# Power.net
KiCad netlist of a schematic drawn in Altium Designer
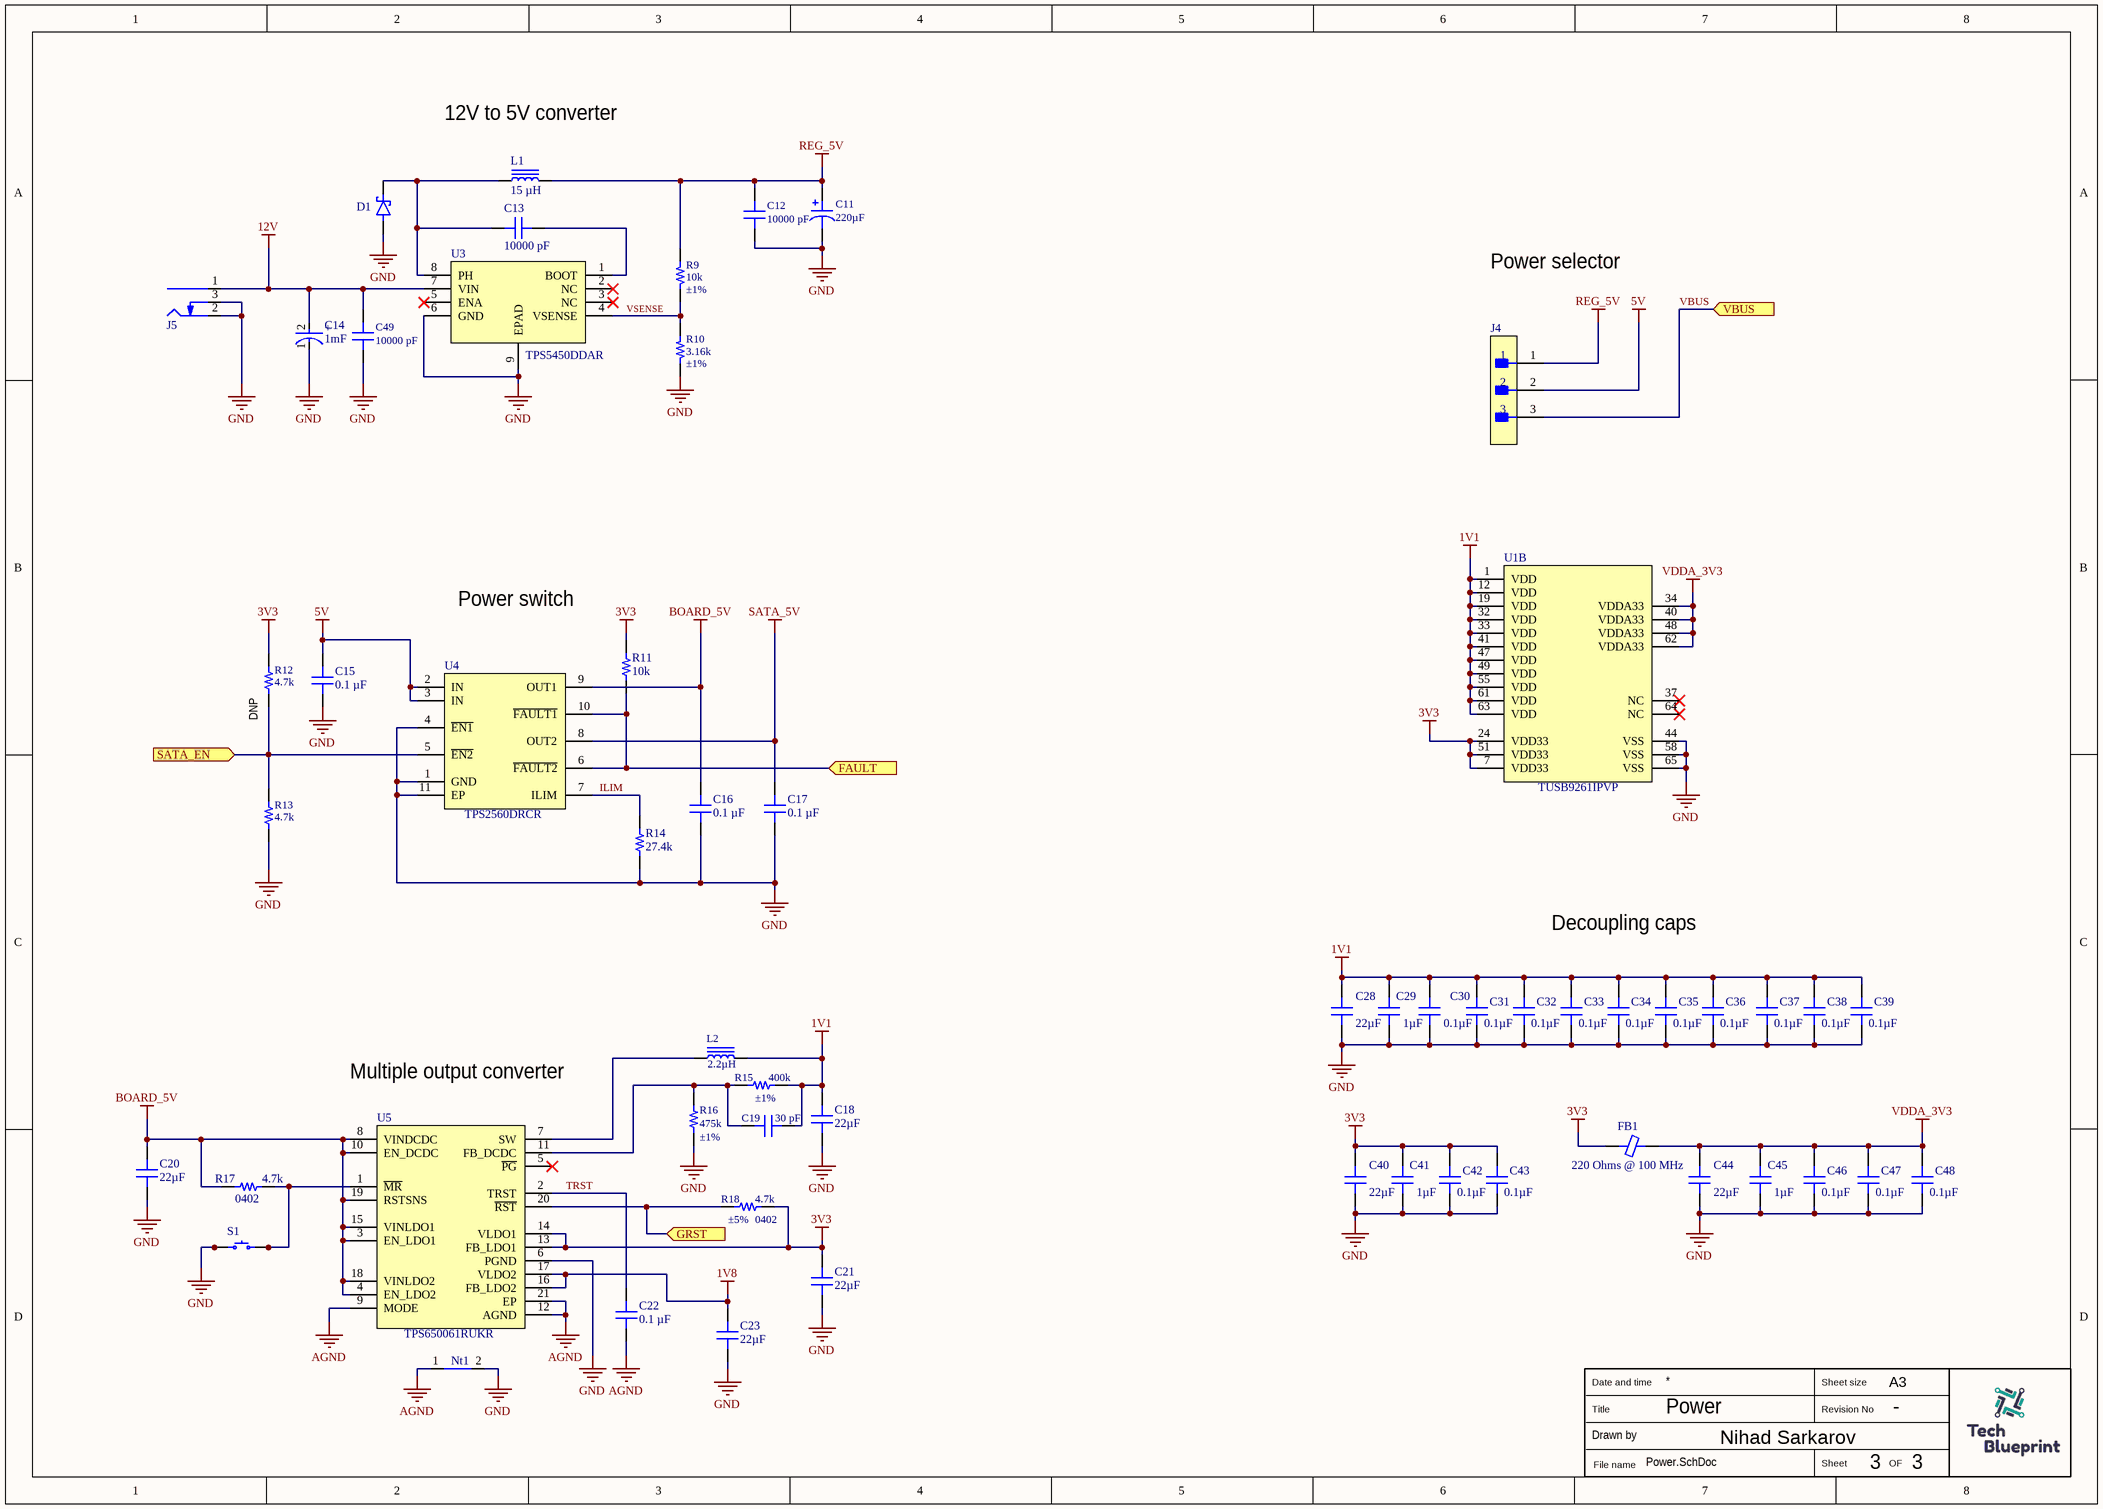
[diagram p0: Power.SchDoc]

(export (version "E")
  (design (tool "Eeschema 10.0.6"))
  (components
    (comp (ref "C11")
      (value "220µF")
      (footprint "CAP ALSMD 8.3MM H10.5MM")
      (description "CAP ALUM 220UF 20% 25V SMD")
      (fields (field (name "PART NUMBER") "UUR1E221MNL6GS") (field (name "MANUFACTURER") "Nichicon"))
      (libsource (lib "Celestial Altium Library - altium_library") (part "Polarised Capacitor"))
    )
    (comp (ref "C12")
      (value "10000 pF")
      (footprint "CAP 0805_2012")
      (description "CAP CER 0805 10NF 100V X7R")
      (fields
        (field (name "PART NUMBER") "C0805X103K1RAC3316")
        (field (name "CAPACITANCE") "10000 pF")
        (field (name "MANUFACTURER") "KEMET")
      )
      (libsource (lib "Celestial Altium Library - altium_library") (part "Capacitor"))
    )
    (comp (ref "C13")
      (value "10000 pF")
      (footprint "CAP 0805_2012")
      (description "CAP CER 0805 10NF 100V X7R")
      (fields
        (field (name "PART NUMBER") "C0805X103K1RAC3316")
        (field (name "CAPACITANCE") "10000 pF")
        (field (name "MANUFACTURER") "KEMET")
      )
      (libsource (lib "Celestial Altium Library - altium_library") (part "Capacitor"))
    )
    (comp (ref "C14")
      (value "EEEFT1C102AP")
      (footprint "FP-FTG-MFG")
      (description "CAP ALUM 1000UF 20% 16V SMD")
      (fields
        (field (name "TOLERANCE") "20%")
        (field (name "CAPACITANCE") "1mF")
        (field (name "VOLTAGE") "16V")
      )
      (libsource (lib "Altium Content Vault") (part "a00bbbee19879c290e62620ae7e47b1"))
    )
    (comp (ref "C15")
      (value "0.1 µF")
      (footprint "CAP 0603_1608")
      (description "CAP CER 0.1UF 50V X7R 0603")
      (fields
        (field (name "PART NUMBER") "CL10B104KB85PND")
        (field (name "CAPACITANCE") "0.1 µF")
        (field (name "MANUFACTURER") "Samsung Electro-Mechanics")
      )
      (libsource (lib "Celestial Altium Library - altium_library") (part "Capacitor"))
    )
    (comp (ref "C16")
      (value "0.1 µF")
      (footprint "CAP 0603_1608")
      (description "CAP CER 0.1UF 50V X7R 0603")
      (fields
        (field (name "PART NUMBER") "CL10B104KB85PND")
        (field (name "CAPACITANCE") "0.1 µF")
        (field (name "MANUFACTURER") "Samsung Electro-Mechanics")
      )
      (libsource (lib "Celestial Altium Library - altium_library") (part "Capacitor"))
    )
    (comp (ref "C17")
      (value "0.1 µF")
      (footprint "CAP 0603_1608")
      (description "CAP CER 0.1UF 50V X7R 0603")
      (fields
        (field (name "PART NUMBER") "CL10B104KB85PND")
        (field (name "CAPACITANCE") "0.1 µF")
        (field (name "MANUFACTURER") "Samsung Electro-Mechanics")
      )
      (libsource (lib "Celestial Altium Library - altium_library") (part "Capacitor"))
    )
    (comp (ref "C18")
      (value "22µF")
      (footprint "CAP 1206_3216 - 1.8MM")
      (description "CAP CER 22UF 16V X5R 1206")
      (fields
        (field (name "PART NUMBER") "1206YD226KAT2A")
        (field (name "CAPACITANCE") "22µF")
        (field (name "MANUFACTURER") "AVX Corporation")
      )
      (libsource (lib "Celestial Altium Library - altium_library") (part "Capacitor"))
    )
    (comp (ref "C19")
      (value "30 pF")
      (footprint "CAP 0402_1005")
      (description "CAP CER 30PF 50V NP0 0402")
      (fields
        (field (name "PART NUMBER") "C0402C300K5GAC7867")
        (field (name "CAPACITANCE") "30 pF")
        (field (name "MANUFACTURER") "KEMET")
      )
      (libsource (lib "Celestial Altium Library - altium_library") (part "Capacitor"))
    )
    (comp (ref "C20")
      (value "22µF")
      (footprint "CAP 1206_3216 - 1.8MM")
      (description "CAP CER 22UF 16V X5R 1206")
      (fields
        (field (name "PART NUMBER") "1206YD226KAT2A")
        (field (name "CAPACITANCE") "22µF")
        (field (name "MANUFACTURER") "AVX Corporation")
      )
      (libsource (lib "Celestial Altium Library - altium_library") (part "Capacitor"))
    )
    (comp (ref "C21")
      (value "22µF")
      (footprint "CAP 1206_3216 - 1.8MM")
      (description "CAP CER 22UF 16V X5R 1206")
      (fields
        (field (name "PART NUMBER") "1206YD226KAT2A")
        (field (name "CAPACITANCE") "22µF")
        (field (name "MANUFACTURER") "AVX Corporation")
      )
      (libsource (lib "Celestial Altium Library - altium_library") (part "Capacitor"))
    )
    (comp (ref "C22")
      (value "0.1 µF")
      (footprint "CAP 0603_1608")
      (description "CAP CER 0.1UF 50V X7R 0603")
      (fields
        (field (name "PART NUMBER") "CL10B104KB85PND")
        (field (name "CAPACITANCE") "0.1 µF")
        (field (name "MANUFACTURER") "Samsung Electro-Mechanics")
      )
      (libsource (lib "Celestial Altium Library - altium_library") (part "Capacitor"))
    )
    (comp (ref "C23")
      (value "22µF")
      (footprint "CAP 1206_3216 - 1.8MM")
      (description "CAP CER 22UF 16V X5R 1206")
      (fields
        (field (name "PART NUMBER") "1206YD226KAT2A")
        (field (name "CAPACITANCE") "22µF")
        (field (name "MANUFACTURER") "AVX Corporation")
      )
      (libsource (lib "Celestial Altium Library - altium_library") (part "Capacitor"))
    )
    (comp (ref "C28")
      (value "22µF")
      (footprint "CAP 1206_3216 - 1.8MM")
      (description "CAP CER 22UF 16V X5R 1206")
      (fields
        (field (name "PART NUMBER") "1206YD226KAT2A")
        (field (name "CAPACITANCE") "22µF")
        (field (name "MANUFACTURER") "AVX Corporation")
      )
      (libsource (lib "Celestial Altium Library - altium_library") (part "Capacitor"))
    )
    (comp (ref "C29")
      (value "1µF")
      (footprint "CAP 0805_2012")
      (description "CAP CER 1UF 10V X7R 0805")
      (fields
        (field (name "PART NUMBER") "MM05ZC105KCZ2A")
        (field (name "CAPACITANCE") "1µF")
        (field (name "MANUFACTURER") "AVX Corporation")
      )
      (libsource (lib "Celestial Altium Library - altium_library") (part "Capacitor"))
    )
    (comp (ref "C30")
      (value "0.1µF")
      (footprint "CAP 0805_2012")
      (description "CAP CER 0.1UF 25V X7R 0805")
      (fields
        (field (name "PART NUMBER") "08053C104KAT4A")
        (field (name "CAPACITANCE") "0.1µF")
        (field (name "MANUFACTURER") "AVX Corporation")
      )
      (libsource (lib "Celestial Altium Library - altium_library") (part "Capacitor"))
    )
    (comp (ref "C31")
      (value "0.1µF")
      (footprint "CAP 0603_1608")
      (description "CAP CER 0.1UF 25V X7R 0603")
      (fields
        (field (name "PART NUMBER") "06033C104K4T4A")
        (field (name "CAPACITANCE") "0.1µF")
        (field (name "MANUFACTURER") "AVX Corporation")
      )
      (libsource (lib "Celestial Altium Library - altium_library") (part "Capacitor"))
    )
    (comp (ref "C32")
      (value "0.1µF")
      (footprint "CAP 0603_1608")
      (description "CAP CER 0.1UF 25V X7R 0603")
      (fields
        (field (name "PART NUMBER") "06033C104K4T4A")
        (field (name "CAPACITANCE") "0.1µF")
        (field (name "MANUFACTURER") "AVX Corporation")
      )
      (libsource (lib "Celestial Altium Library - altium_library") (part "Capacitor"))
    )
    (comp (ref "C33")
      (value "0.1µF")
      (footprint "CAP 0603_1608")
      (description "CAP CER 0.1UF 25V X7R 0603")
      (fields
        (field (name "PART NUMBER") "06033C104K4T4A")
        (field (name "CAPACITANCE") "0.1µF")
        (field (name "MANUFACTURER") "AVX Corporation")
      )
      (libsource (lib "Celestial Altium Library - altium_library") (part "Capacitor"))
    )
    (comp (ref "C34")
      (value "0.1µF")
      (footprint "CAP 0603_1608")
      (description "CAP CER 0.1UF 25V X7R 0603")
      (fields
        (field (name "PART NUMBER") "06033C104K4T4A")
        (field (name "CAPACITANCE") "0.1µF")
        (field (name "MANUFACTURER") "AVX Corporation")
      )
      (libsource (lib "Celestial Altium Library - altium_library") (part "Capacitor"))
    )
    (comp (ref "C35")
      (value "0.1µF")
      (footprint "CAP 0603_1608")
      (description "CAP CER 0.1UF 25V X7R 0603")
      (fields
        (field (name "PART NUMBER") "06033C104K4T4A")
        (field (name "CAPACITANCE") "0.1µF")
        (field (name "MANUFACTURER") "AVX Corporation")
      )
      (libsource (lib "Celestial Altium Library - altium_library") (part "Capacitor"))
    )
    (comp (ref "C36")
      (value "0.1µF")
      (footprint "CAP 0603_1608")
      (description "CAP CER 0.1UF 25V X7R 0603")
      (fields
        (field (name "PART NUMBER") "06033C104K4T4A")
        (field (name "CAPACITANCE") "0.1µF")
        (field (name "MANUFACTURER") "AVX Corporation")
      )
      (libsource (lib "Celestial Altium Library - altium_library") (part "Capacitor"))
    )
    (comp (ref "C37")
      (value "0.1µF")
      (footprint "CAP 0603_1608")
      (description "CAP CER 0.1UF 25V X7R 0603")
      (fields
        (field (name "PART NUMBER") "06033C104K4T4A")
        (field (name "CAPACITANCE") "0.1µF")
        (field (name "MANUFACTURER") "AVX Corporation")
      )
      (libsource (lib "Celestial Altium Library - altium_library") (part "Capacitor"))
    )
    (comp (ref "C38")
      (value "0.1µF")
      (footprint "CAP 0603_1608")
      (description "CAP CER 0.1UF 25V X7R 0603")
      (fields
        (field (name "PART NUMBER") "06033C104K4T4A")
        (field (name "CAPACITANCE") "0.1µF")
        (field (name "MANUFACTURER") "AVX Corporation")
      )
      (libsource (lib "Celestial Altium Library - altium_library") (part "Capacitor"))
    )
    (comp (ref "C39")
      (value "0.1µF")
      (footprint "CAP 0603_1608")
      (description "CAP CER 0.1UF 25V X7R 0603")
      (fields
        (field (name "PART NUMBER") "06033C104K4T4A")
        (field (name "CAPACITANCE") "0.1µF")
        (field (name "MANUFACTURER") "AVX Corporation")
      )
      (libsource (lib "Celestial Altium Library - altium_library") (part "Capacitor"))
    )
    (comp (ref "C40")
      (value "22µF")
      (footprint "CAP 1206_3216 - 1.8MM")
      (description "CAP CER 22UF 16V X5R 1206")
      (fields
        (field (name "PART NUMBER") "1206YD226KAT2A")
        (field (name "CAPACITANCE") "22µF")
        (field (name "MANUFACTURER") "AVX Corporation")
      )
      (libsource (lib "Celestial Altium Library - altium_library") (part "Capacitor"))
    )
    (comp (ref "C41")
      (value "1µF")
      (footprint "CAP 0805_2012")
      (description "CAP CER 1UF 10V X7R 0805")
      (fields
        (field (name "PART NUMBER") "MM05ZC105KCZ2A")
        (field (name "CAPACITANCE") "1µF")
        (field (name "MANUFACTURER") "AVX Corporation")
      )
      (libsource (lib "Celestial Altium Library - altium_library") (part "Capacitor"))
    )
    (comp (ref "C42")
      (value "0.1µF")
      (footprint "CAP 0603_1608")
      (description "CAP CER 0.1UF 25V X7R 0603")
      (fields
        (field (name "PART NUMBER") "06033C104K4T4A")
        (field (name "CAPACITANCE") "0.1µF")
        (field (name "MANUFACTURER") "AVX Corporation")
      )
      (libsource (lib "Celestial Altium Library - altium_library") (part "Capacitor"))
    )
    (comp (ref "C43")
      (value "0.1µF")
      (footprint "CAP 0603_1608")
      (description "CAP CER 0.1UF 25V X7R 0603")
      (fields
        (field (name "PART NUMBER") "06033C104K4T4A")
        (field (name "CAPACITANCE") "0.1µF")
        (field (name "MANUFACTURER") "AVX Corporation")
      )
      (libsource (lib "Celestial Altium Library - altium_library") (part "Capacitor"))
    )
    (comp (ref "C44")
      (value "22µF")
      (footprint "CAP 1206_3216 - 1.8MM")
      (description "CAP CER 22UF 16V X5R 1206")
      (fields
        (field (name "PART NUMBER") "1206YD226KAT2A")
        (field (name "CAPACITANCE") "22µF")
        (field (name "MANUFACTURER") "AVX Corporation")
      )
      (libsource (lib "Celestial Altium Library - altium_library") (part "Capacitor"))
    )
    (comp (ref "C45")
      (value "1µF")
      (footprint "CAP 0805_2012")
      (description "CAP CER 1UF 10V X7R 0805")
      (fields
        (field (name "PART NUMBER") "MM05ZC105KCZ2A")
        (field (name "CAPACITANCE") "1µF")
        (field (name "MANUFACTURER") "AVX Corporation")
      )
      (libsource (lib "Celestial Altium Library - altium_library") (part "Capacitor"))
    )
    (comp (ref "C46")
      (value "0.1µF")
      (footprint "CAP 0603_1608")
      (description "CAP CER 0.1UF 25V X7R 0603")
      (fields
        (field (name "PART NUMBER") "06033C104K4T4A")
        (field (name "CAPACITANCE") "0.1µF")
        (field (name "MANUFACTURER") "AVX Corporation")
      )
      (libsource (lib "Celestial Altium Library - altium_library") (part "Capacitor"))
    )
    (comp (ref "C47")
      (value "0.1µF")
      (footprint "CAP 0603_1608")
      (description "CAP CER 0.1UF 25V X7R 0603")
      (fields
        (field (name "PART NUMBER") "06033C104K4T4A")
        (field (name "CAPACITANCE") "0.1µF")
        (field (name "MANUFACTURER") "AVX Corporation")
      )
      (libsource (lib "Celestial Altium Library - altium_library") (part "Capacitor"))
    )
    (comp (ref "C48")
      (value "0.1µF")
      (footprint "CAP 0603_1608")
      (description "CAP CER 0.1UF 25V X7R 0603")
      (fields
        (field (name "PART NUMBER") "06033C104K4T4A")
        (field (name "CAPACITANCE") "0.1µF")
        (field (name "MANUFACTURER") "AVX Corporation")
      )
      (libsource (lib "Celestial Altium Library - altium_library") (part "Capacitor"))
    )
    (comp (ref "C49")
      (value "10000 pF")
      (footprint "CAP 0805_2012")
      (description "CAP CER 0805 10NF 100V X7R")
      (fields
        (field (name "PART NUMBER") "C0805X103K1RAC3316")
        (field (name "CAPACITANCE") "10000 pF")
        (field (name "MANUFACTURER") "KEMET")
      )
      (libsource (lib "Celestial Altium Library - altium_library") (part "Capacitor"))
    )
    (comp (ref "D1")
      (value "MBRS540T3G")
      (footprint "MBRS540T3G:DIOM7959X261N")
      (fields (field (name "MF") "{'manufacturer': u'ON Semiconductor'}"))
      (libsource (lib "USB to SATA") (part "MBRS540T3G"))
    )
    (comp (ref "FB1")
      (value "220 Ohms @ 100 MHz")
      (footprint "FER 0603_1608")
      (description "POWER LINE HIGH IMPEDANCE FERRIT")
      (fields (field (name "PART NUMBER") "Z0603C221BPWZT") (field (name "MANUFACTURER") "KEMET"))
      (libsource (lib "Celestial Altium Library - altium_library") (part "Ferrite Chip"))
    )
    (comp (ref "J4")
      (value "87224-3")
      (footprint "FP-87224-3-MFG")
      (description "CONN HEADER VERT 3POS 2.54MM")
      (libsource (lib "USB to SATA") (part "CMP-2000-05697-2"))
    )
    (comp (ref "J5")
      (value "PJ-002AH-SMT-TR")
      (footprint "CUI PJ-002AH-SMT-TR")
      (description "CONN PWR JACK 2X5.5MM SOLDER")
      (fields (field (name "MANUFACTURER") "CUI Devices"))
      (libsource (lib "Celestial Altium Library - altium_library") (part "Barrel Connector"))
    )
    (comp (ref "L1")
      (value "15 µH")
      (footprint "BOURNS SRR1280")
      (description "FIXED IND 15UH 5.2A 28.5MOHM SMD")
      (fields (field (name "PART NUMBER") "SRR1280-150M") (field (name "MANUFACTURER") "Bourns Inc."))
      (libsource (lib "") (part "Inductor_1"))
    )
    (comp (ref "L2")
      (value "2.2µH")
      (footprint "IND 1008_2520")
      (description "FIXED IND 2.2UH 700MA 150 MOHM")
      (fields (field (name "PART NUMBER") "CKP2520V2R2M-T") (field (name "MANUFACTURER") "Taiyo Yuden"))
      (libsource (lib "Celestial Altium Library - altium_library") (part "Inductor"))
    )
    (comp (ref "Nt1")
      (value "Net tie")
      (footprint "Net tie")
      (description "Net tie SMD")
      (libsource (lib "USB to SATA") (part "Net tie"))
    )
    (comp (ref "R9")
      (value "10k")
      (footprint "YAGEO RES 0603_1608")
      (description "RES SMD 10K OHM 1% 1/10W 0603")
      (fields
        (field (name "PART NUMBER") "RT0603FRE0710KL")
        (field (name "MANUFACTURER") "Yageo")
        (field (name "TOLERANCE") "±1%")
      )
      (libsource (lib "Celestial Altium Library - altium_library") (part "Resistor"))
    )
    (comp (ref "R10")
      (value "3.16k")
      (footprint "RES 0603_1608")
      (description "RES SMD 3.16K OHM 1% 1/10W 0603")
      (fields
        (field (name "PART NUMBER") "CR0603-FX-3161ELF")
        (field (name "MANUFACTURER") "Bourns Inc.")
        (field (name "TOLERANCE") "±1%")
      )
      (libsource (lib "Celestial Altium Library - altium_library") (part "Resistor"))
    )
    (comp (ref "R11")
      (value "10k")
      (footprint "YAGEO RES 0402_1005")
      (description "RES SMD 10K OHM 5% 1/16W 0402")
      (fields (field (name "PART NUMBER") "AC0402JR-0710KL") (field (name "MANUFACTURER") "Yageo"))
      (libsource (lib "Celestial Altium Library - altium_library") (part "Resistor"))
    )
    (comp (ref "R12")
      (value "4.7k")
      (footprint "RES 0603_1608")
      (description "RES 4.7K OHM 5% 1/10W 0603")
      (fields
        (field (name "PART NUMBER") "RMCF0603JT4K70")
        (field (name "MANUFACTURER") "Stackpole Electronics Inc")
      )
      (libsource (lib "Celestial Altium Library - altium_library") (part "Resistor"))
    )
    (comp (ref "R13")
      (value "4.7k")
      (footprint "RES 0603_1608")
      (description "RES 4.7K OHM 5% 1/10W 0603")
      (fields
        (field (name "PART NUMBER") "RMCF0603JT4K70")
        (field (name "MANUFACTURER") "Stackpole Electronics Inc")
      )
      (libsource (lib "Celestial Altium Library - altium_library") (part "Resistor"))
    )
    (comp (ref "R14")
      (value "27.4k")
      (footprint "RES 0402_1005")
      (description "RES SMD 27.4K OHM 1% 1/10W 0402")
      (fields
        (field (name "PART NUMBER") "ERJ-2RKF2742X")
        (field (name "MANUFACTURER") "Panasonic Electronic Components")
      )
      (libsource (lib "Celestial Altium Library - altium_library") (part "Resistor"))
    )
    (comp (ref "R15")
      (value "400k")
      (footprint "KOA RES RK73 RN73 0402_1005")
      (description "RES 400K OHM 1% 1/10W 0402")
      (fields
        (field (name "PART NUMBER") "RK73H1ETTP4123F")
        (field (name "MANUFACTURER") "KOA Speer Electronics, Inc.")
        (field (name "TOLERANCE") "±1%")
      )
      (libsource (lib "Celestial Altium Library - altium_library") (part "Resistor"))
    )
    (comp (ref "R16")
      (value "475k")
      (footprint "RES 0402_1005")
      (description "RES 475K OHM 1% 1/16W 0402")
      (fields
        (field (name "PART NUMBER") "RMCF0402FT475K")
        (field (name "MANUFACTURER") "Stackpole Electronics Inc")
        (field (name "TOLERANCE") "±1%")
      )
      (libsource (lib "Celestial Altium Library - altium_library") (part "Resistor"))
    )
    (comp (ref "R17")
      (value "4.7k")
      (footprint "YAGEO RES 0402_1005")
      (description "RES SMD 4.7K OHM 5% 1/16W 0402")
      (fields
        (field (name "PART NUMBER") "AC0402JR-074K7L")
        (field (name "MANUFACTURER") "Yageo")
        (field (name "SUPPLIER DEVICE PACKAGE") "0402")
      )
      (libsource (lib "Celestial Altium Library - altium_library") (part "Resistor"))
    )
    (comp (ref "R18")
      (value "4.7k")
      (footprint "YAGEO RES 0402_1005")
      (description "RES SMD 4.7K OHM 5% 1/16W 0402")
      (fields
        (field (name "PART NUMBER") "AC0402JR-074K7L")
        (field (name "MANUFACTURER") "Yageo")
        (field (name "SUPPLIER DEVICE PACKAGE") "0402")
        (field (name "TOLERANCE") "±5%")
      )
      (libsource (lib "Celestial Altium Library - altium_library") (part "Resistor"))
    )
    (comp (ref "S1")
      (value "PTS645SM43SMTR92 LFS")
      (footprint "C&K PTS645")
      (description "SWITCH TACTILE SPST-NO 0.05A 12V")
      (fields (field (name "MANUFACTURER") "C&K"))
      (libsource (lib "Celestial Altium Library - altium_library") (part "SPST-NO 4 PIN"))
    )
    (comp (ref "U1")
      (value "TUSB9261IPVP")
      (footprint "FP-PVP0064A-IPC_A")
      (description "HDD, CD, DVD Drive Interface 64-HTQFP (7x7)")
      (fields
        (field (name "MANUFACTURER") "Texas Instruments")
        (field (name "DIGIKEY PART NUMBER") "296-35545-ND")
      )
      (libsource (lib "USB to SATA") (part "TUSB9261IPVP"))
    )
    (comp (ref "U3")
      (value "TPS5450DDAR")
      (footprint "FP-DDA0008J-IPC_A")
      (description "IC REG BUCK ADJUSTABLE 5A 8SOPWR")
      (fields
        (field (name "MANUFACTURER") "Texas Instruments")
        (field (name "OCTOPART") "https://octopart.com/tps5450ddar-texas+instruments-7105511")
      )
      (libsource (lib "USB to SATA") (part "CMP-04918-000100-1"))
    )
    (comp (ref "U4")
      (value "TPS2560DRCR")
      (footprint "FP-DRC0010J-IPC_A")
      (description "IC PWR SWITCH N-CHAN 1:2 10VSON")
      (libsource (lib "USB to SATA") (part "CMP-0337-00200-3"))
    )
    (comp (ref "U5")
      (value "TPS650061RUKR")
      (footprint "RUK0020B")
      (fields (field (name "MANUFACTURER") "Texas Instruments"))
      (libsource (lib "USB to SATA") (part "CMP-1518-00013-2"))
    )
  )
  (nets
    (net (code "1") (name "/FAULT") (class "Default")
      (node (ref "R11") (pin "1") (pinfunction "1_1") (pintype "passive"))
      (node (ref "U4") (pin "10") (pinfunction "~{FAULT1}_10") (pintype "tri_state"))
      (node (ref "U4") (pin "6") (pinfunction "~{FAULT2}_6") (pintype "tri_state"))
    )
    (net (code "2") (name "/GRST") (class "Default")
      (node (ref "R18") (pin "1") (pinfunction "1_1") (pintype "passive"))
      (node (ref "U5") (pin "20") (pinfunction "~{RST}_20") (pintype "passive"))
    )
    (net (code "3") (name "/ILIM") (class "Default")
      (node (ref "R14") (pin "2") (pinfunction "2_2") (pintype "passive"))
      (node (ref "U4") (pin "7") (pinfunction "ILIM_7") (pintype "passive"))
    )
    (net (code "4") (name "/SATA_EN") (class "Default")
      (node (ref "R12") (pin "1") (pinfunction "1_1") (pintype "passive"))
      (node (ref "R13") (pin "2") (pinfunction "2_2") (pintype "passive"))
      (node (ref "U4") (pin "5") (pinfunction "~{EN2}_5") (pintype "passive"))
    )
    (net (code "5") (name "/TRST") (class "Default")
      (node (ref "C22") (pin "2") (pinfunction "2_2") (pintype "passive"))
      (node (ref "U5") (pin "2") (pinfunction "TRST_2") (pintype "passive"))
    )
    (net (code "6") (name "/VBUS") (class "Default")
      (node (ref "J4") (pin "3") (pinfunction "3_3") (pintype "passive"))
    )
    (net (code "7") (name "/VSENSE") (class "Default")
      (node (ref "R10") (pin "2") (pinfunction "2_2") (pintype "passive"))
      (node (ref "R9") (pin "1") (pinfunction "1_1") (pintype "passive"))
      (node (ref "U3") (pin "4") (pinfunction "VSENSE_4") (pintype "passive"))
    )
    (net (code "8") (name "1V1") (class "Default")
      (node (ref "C18") (pin "2") (pinfunction "2_2") (pintype "passive"))
      (node (ref "C19") (pin "2") (pinfunction "2_2") (pintype "passive"))
      (node (ref "C28") (pin "2") (pinfunction "2_2") (pintype "passive"))
      (node (ref "C29") (pin "2") (pinfunction "2_2") (pintype "passive"))
      (node (ref "C30") (pin "2") (pinfunction "2_2") (pintype "passive"))
      (node (ref "C31") (pin "2") (pinfunction "2_2") (pintype "passive"))
      (node (ref "C32") (pin "2") (pinfunction "2_2") (pintype "passive"))
      (node (ref "C33") (pin "2") (pinfunction "2_2") (pintype "passive"))
      (node (ref "C34") (pin "2") (pinfunction "2_2") (pintype "passive"))
      (node (ref "C35") (pin "2") (pinfunction "2_2") (pintype "passive"))
      (node (ref "C36") (pin "2") (pinfunction "2_2") (pintype "passive"))
      (node (ref "C37") (pin "2") (pinfunction "2_2") (pintype "passive"))
      (node (ref "C38") (pin "2") (pinfunction "2_2") (pintype "passive"))
      (node (ref "C39") (pin "2") (pinfunction "2_2") (pintype "passive"))
      (node (ref "L2") (pin "2") (pinfunction "2_2") (pintype "passive"))
      (node (ref "R15") (pin "2") (pinfunction "2_2") (pintype "passive"))
      (node (ref "U1") (pin "1") (pinfunction "VDD_1") (pintype "passive"))
      (node (ref "U1") (pin "12") (pinfunction "VDD_12") (pintype "passive"))
      (node (ref "U1") (pin "19") (pinfunction "VDD_19") (pintype "passive"))
      (node (ref "U1") (pin "32") (pinfunction "VDD_32") (pintype "passive"))
      (node (ref "U1") (pin "33") (pinfunction "VDD_33") (pintype "passive"))
      (node (ref "U1") (pin "41") (pinfunction "VDD_41") (pintype "passive"))
      (node (ref "U1") (pin "47") (pinfunction "VDD_47") (pintype "passive"))
      (node (ref "U1") (pin "49") (pinfunction "VDD_49") (pintype "passive"))
      (node (ref "U1") (pin "55") (pinfunction "VDD_55") (pintype "passive"))
      (node (ref "U1") (pin "61") (pinfunction "VDD_61") (pintype "passive"))
      (node (ref "U1") (pin "63") (pinfunction "VDD_63") (pintype "passive"))
    )
    (net (code "9") (name "1V8") (class "Default")
      (node (ref "C23") (pin "2") (pinfunction "2_2") (pintype "passive"))
      (node (ref "U5") (pin "16") (pinfunction "FB_LDO2_16") (pintype "passive"))
      (node (ref "U5") (pin "17") (pinfunction "VLDO2_17") (pintype "passive"))
    )
    (net (code "10") (name "3V3") (class "Default")
      (node (ref "C21") (pin "2") (pinfunction "2_2") (pintype "passive"))
      (node (ref "C40") (pin "2") (pinfunction "2_2") (pintype "passive"))
      (node (ref "C41") (pin "2") (pinfunction "2_2") (pintype "passive"))
      (node (ref "C42") (pin "2") (pinfunction "2_2") (pintype "passive"))
      (node (ref "C43") (pin "2") (pinfunction "2_2") (pintype "passive"))
      (node (ref "FB1") (pin "1") (pinfunction "1_1") (pintype "passive"))
      (node (ref "R11") (pin "2") (pinfunction "2_2") (pintype "passive"))
      (node (ref "R12") (pin "2") (pinfunction "2_2") (pintype "passive"))
      (node (ref "R18") (pin "2") (pinfunction "2_2") (pintype "passive"))
      (node (ref "U1") (pin "24") (pinfunction "VDD33_24") (pintype "passive"))
      (node (ref "U1") (pin "51") (pinfunction "VDD33_51") (pintype "passive"))
      (node (ref "U1") (pin "7") (pinfunction "VDD33_7") (pintype "passive"))
      (node (ref "U5") (pin "13") (pinfunction "FB_LDO1_13") (pintype "passive"))
      (node (ref "U5") (pin "14") (pinfunction "VLDO1_14") (pintype "passive"))
    )
    (net (code "11") (name "5V") (class "Default")
      (node (ref "C15") (pin "2") (pinfunction "2_2") (pintype "passive"))
      (node (ref "J4") (pin "2") (pinfunction "2_2") (pintype "passive"))
      (node (ref "U4") (pin "2") (pinfunction "IN_2") (pintype "power_in"))
      (node (ref "U4") (pin "3") (pinfunction "IN_3") (pintype "power_in"))
    )
    (net (code "12") (name "12V") (class "Default")
      (node (ref "C14") (pin "2") (pinfunction "A_2") (pintype "passive"))
      (node (ref "C49") (pin "2") (pinfunction "2_2") (pintype "passive"))
      (node (ref "J5") (pin "1") (pinfunction "Centre_1") (pintype "passive"))
      (node (ref "U3") (pin "7") (pinfunction "VIN_7") (pintype "passive"))
    )
    (net (code "13") (name "AGND") (class "Default")
      (node (ref "C22") (pin "1") (pinfunction "1_1") (pintype "passive"))
      (node (ref "Nt1") (pin "1") (pinfunction "1_1") (pintype "passive"))
      (node (ref "U5") (pin "12") (pinfunction "AGND_12") (pintype "passive"))
      (node (ref "U5") (pin "21") (pinfunction "EP_21") (pintype "passive"))
      (node (ref "U5") (pin "9") (pinfunction "MODE_9") (pintype "passive"))
    )
    (net (code "14") (name "BOARD_5V") (class "Default")
      (node (ref "C16") (pin "2") (pinfunction "2_2") (pintype "passive"))
      (node (ref "C20") (pin "2") (pinfunction "2_2") (pintype "passive"))
      (node (ref "R17") (pin "1") (pinfunction "1_1") (pintype "passive"))
      (node (ref "U4") (pin "9") (pinfunction "OUT1_9") (pintype "passive"))
      (node (ref "U5") (pin "10") (pinfunction "EN_DCDC_10") (pintype "passive"))
      (node (ref "U5") (pin "15") (pinfunction "VINLDO1_15") (pintype "passive"))
      (node (ref "U5") (pin "18") (pinfunction "VINLDO2_18") (pintype "passive"))
      (node (ref "U5") (pin "19") (pinfunction "RSTSNS_19") (pintype "passive"))
      (node (ref "U5") (pin "3") (pinfunction "EN_LDO1_3") (pintype "passive"))
      (node (ref "U5") (pin "4") (pinfunction "EN_LDO2_4") (pintype "passive"))
      (node (ref "U5") (pin "8") (pinfunction "VINDCDC_8") (pintype "passive"))
    )
    (net (code "15") (name "GND") (class "Default")
      (node (ref "C11") (pin "2") (pinfunction "2_2") (pintype "passive"))
      (node (ref "C12") (pin "1") (pinfunction "1_1") (pintype "passive"))
      (node (ref "C14") (pin "1") (pinfunction "C_1") (pintype "passive"))
      (node (ref "C15") (pin "1") (pinfunction "1_1") (pintype "passive"))
      (node (ref "C16") (pin "1") (pinfunction "1_1") (pintype "passive"))
      (node (ref "C17") (pin "1") (pinfunction "1_1") (pintype "passive"))
      (node (ref "C18") (pin "1") (pinfunction "1_1") (pintype "passive"))
      (node (ref "C20") (pin "1") (pinfunction "1_1") (pintype "passive"))
      (node (ref "C21") (pin "1") (pinfunction "1_1") (pintype "passive"))
      (node (ref "C23") (pin "1") (pinfunction "1_1") (pintype "passive"))
      (node (ref "C28") (pin "1") (pinfunction "1_1") (pintype "passive"))
      (node (ref "C29") (pin "1") (pinfunction "1_1") (pintype "passive"))
      (node (ref "C30") (pin "1") (pinfunction "1_1") (pintype "passive"))
      (node (ref "C31") (pin "1") (pinfunction "1_1") (pintype "passive"))
      (node (ref "C32") (pin "1") (pinfunction "1_1") (pintype "passive"))
      (node (ref "C33") (pin "1") (pinfunction "1_1") (pintype "passive"))
      (node (ref "C34") (pin "1") (pinfunction "1_1") (pintype "passive"))
      (node (ref "C35") (pin "1") (pinfunction "1_1") (pintype "passive"))
      (node (ref "C36") (pin "1") (pinfunction "1_1") (pintype "passive"))
      (node (ref "C37") (pin "1") (pinfunction "1_1") (pintype "passive"))
      (node (ref "C38") (pin "1") (pinfunction "1_1") (pintype "passive"))
      (node (ref "C39") (pin "1") (pinfunction "1_1") (pintype "passive"))
      (node (ref "C40") (pin "1") (pinfunction "1_1") (pintype "passive"))
      (node (ref "C41") (pin "1") (pinfunction "1_1") (pintype "passive"))
      (node (ref "C42") (pin "1") (pinfunction "1_1") (pintype "passive"))
      (node (ref "C43") (pin "1") (pinfunction "1_1") (pintype "passive"))
      (node (ref "C44") (pin "1") (pinfunction "1_1") (pintype "passive"))
      (node (ref "C45") (pin "1") (pinfunction "1_1") (pintype "passive"))
      (node (ref "C46") (pin "1") (pinfunction "1_1") (pintype "passive"))
      (node (ref "C47") (pin "1") (pinfunction "1_1") (pintype "passive"))
      (node (ref "C48") (pin "1") (pinfunction "1_1") (pintype "passive"))
      (node (ref "C49") (pin "1") (pinfunction "1_1") (pintype "passive"))
      (node (ref "D1") (pin "2") (pinfunction "A_2") (pintype "passive"))
      (node (ref "J5") (pin "2") (pinfunction "Outer_2") (pintype "passive"))
      (node (ref "J5") (pin "3") (pinfunction "SW_3") (pintype "passive"))
      (node (ref "Nt1") (pin "2") (pinfunction "2_2") (pintype "passive"))
      (node (ref "R10") (pin "1") (pinfunction "1_1") (pintype "passive"))
      (node (ref "R13") (pin "1") (pinfunction "1_1") (pintype "passive"))
      (node (ref "R14") (pin "1") (pinfunction "1_1") (pintype "passive"))
      (node (ref "R16") (pin "1") (pinfunction "1_1") (pintype "passive"))
      (node (ref "S1") (pin "1") (pinfunction "1_1") (pintype "passive"))
      (node (ref "S1") (pin "2") (pinfunction "2_2") (pintype "passive"))
      (node (ref "U1") (pin "44") (pinfunction "VSS_44") (pintype "passive"))
      (node (ref "U1") (pin "58") (pinfunction "VSS_58") (pintype "passive"))
      (node (ref "U1") (pin "65") (pinfunction "VSS_65") (pintype "passive"))
      (node (ref "U3") (pin "6") (pinfunction "GND_6") (pintype "passive"))
      (node (ref "U3") (pin "9") (pinfunction "EPAD_9") (pintype "power_in"))
      (node (ref "U4") (pin "1") (pinfunction "GND_1") (pintype "passive"))
      (node (ref "U4") (pin "11") (pinfunction "EP_11") (pintype "passive"))
      (node (ref "U4") (pin "4") (pinfunction "~{EN1}_4") (pintype "passive"))
      (node (ref "U5") (pin "6") (pinfunction "PGND_6") (pintype "passive"))
    )
    (net (code "16") (name "Net-(D1-C)") (class "Default")
      (node (ref "C13") (pin "1") (pinfunction "1_1") (pintype "passive"))
      (node (ref "D1") (pin "1") (pinfunction "C_1") (pintype "passive"))
      (node (ref "L1") (pin "2") (pinfunction "2_2") (pintype "passive"))
      (node (ref "U3") (pin "8") (pinfunction "PH_8") (pintype "passive"))
    )
    (net (code "17") (name "Net-(U3-BOOT)") (class "Default")
      (node (ref "C13") (pin "2") (pinfunction "2_2") (pintype "passive"))
      (node (ref "U3") (pin "1") (pinfunction "BOOT_1") (pintype "passive"))
    )
    (net (code "18") (name "Net-(U5-FB_DCDC)") (class "Default")
      (node (ref "C19") (pin "1") (pinfunction "1_1") (pintype "passive"))
      (node (ref "R15") (pin "1") (pinfunction "1_1") (pintype "passive"))
      (node (ref "R16") (pin "2") (pinfunction "2_2") (pintype "passive"))
      (node (ref "U5") (pin "11") (pinfunction "FB_DCDC_11") (pintype "passive"))
    )
    (net (code "19") (name "Net-(U5-SW)") (class "Default")
      (node (ref "L2") (pin "1") (pinfunction "1_1") (pintype "passive"))
      (node (ref "U5") (pin "7") (pinfunction "SW_7") (pintype "passive"))
    )
    (net (code "20") (name "Net-(U5-~{MR})") (class "Default")
      (node (ref "R17") (pin "2") (pinfunction "2_2") (pintype "passive"))
      (node (ref "S1") (pin "3") (pinfunction "3_3") (pintype "passive"))
      (node (ref "S1") (pin "4") (pinfunction "4_4") (pintype "passive"))
      (node (ref "U5") (pin "1") (pinfunction "~{MR}_1") (pintype "passive"))
    )
    (net (code "21") (name "REG_5V") (class "Default")
      (node (ref "C11") (pin "1") (pinfunction "1_1") (pintype "passive"))
      (node (ref "C12") (pin "2") (pinfunction "2_2") (pintype "passive"))
      (node (ref "J4") (pin "1") (pinfunction "1_1") (pintype "passive"))
      (node (ref "L1") (pin "1") (pinfunction "1_1") (pintype "passive"))
      (node (ref "R9") (pin "2") (pinfunction "2_2") (pintype "passive"))
    )
    (net (code "22") (name "SATA_5V") (class "Default")
      (node (ref "C17") (pin "2") (pinfunction "2_2") (pintype "passive"))
      (node (ref "U4") (pin "8") (pinfunction "OUT2_8") (pintype "passive"))
    )
    (net (code "23") (name "VDDA_3V3") (class "Default")
      (node (ref "C44") (pin "2") (pinfunction "2_2") (pintype "passive"))
      (node (ref "C45") (pin "2") (pinfunction "2_2") (pintype "passive"))
      (node (ref "C46") (pin "2") (pinfunction "2_2") (pintype "passive"))
      (node (ref "C47") (pin "2") (pinfunction "2_2") (pintype "passive"))
      (node (ref "C48") (pin "2") (pinfunction "2_2") (pintype "passive"))
      (node (ref "FB1") (pin "2") (pinfunction "2_2") (pintype "passive"))
      (node (ref "U1") (pin "34") (pinfunction "VDDA33_34") (pintype "passive"))
      (node (ref "U1") (pin "40") (pinfunction "VDDA33_40") (pintype "passive"))
      (node (ref "U1") (pin "48") (pinfunction "VDDA33_48") (pintype "passive"))
      (node (ref "U1") (pin "62") (pinfunction "VDDA33_62") (pintype "passive"))
    )
    (net (code "24") (name "unconnected-(U1B-NC-Pad37)") (class "Default")
      (node (ref "U1") (pin "37") (pinfunction "NC_37") (pintype "passive+no_connect"))
    )
    (net (code "25") (name "unconnected-(U1B-NC-Pad64)") (class "Default")
      (node (ref "U1") (pin "64") (pinfunction "NC_64") (pintype "passive+no_connect"))
    )
    (net (code "26") (name "unconnected-(U3-ENA-Pad5)") (class "Default")
      (node (ref "U3") (pin "5") (pinfunction "ENA_5") (pintype "passive+no_connect"))
    )
    (net (code "27") (name "unconnected-(U3-NC-Pad2)") (class "Default")
      (node (ref "U3") (pin "2") (pinfunction "NC_2") (pintype "passive+no_connect"))
    )
    (net (code "28") (name "unconnected-(U3-NC-Pad3)") (class "Default")
      (node (ref "U3") (pin "3") (pinfunction "NC_3") (pintype "passive+no_connect"))
    )
    (net (code "29") (name "unconnected-(U5-~{PG}-Pad5)") (class "Default")
      (node (ref "U5") (pin "5") (pinfunction "~{PG}_5") (pintype "passive+no_connect"))
    )
  )
)
